# 2_POWER.net
KiCad netlist of a schematic drawn in Altium Designer
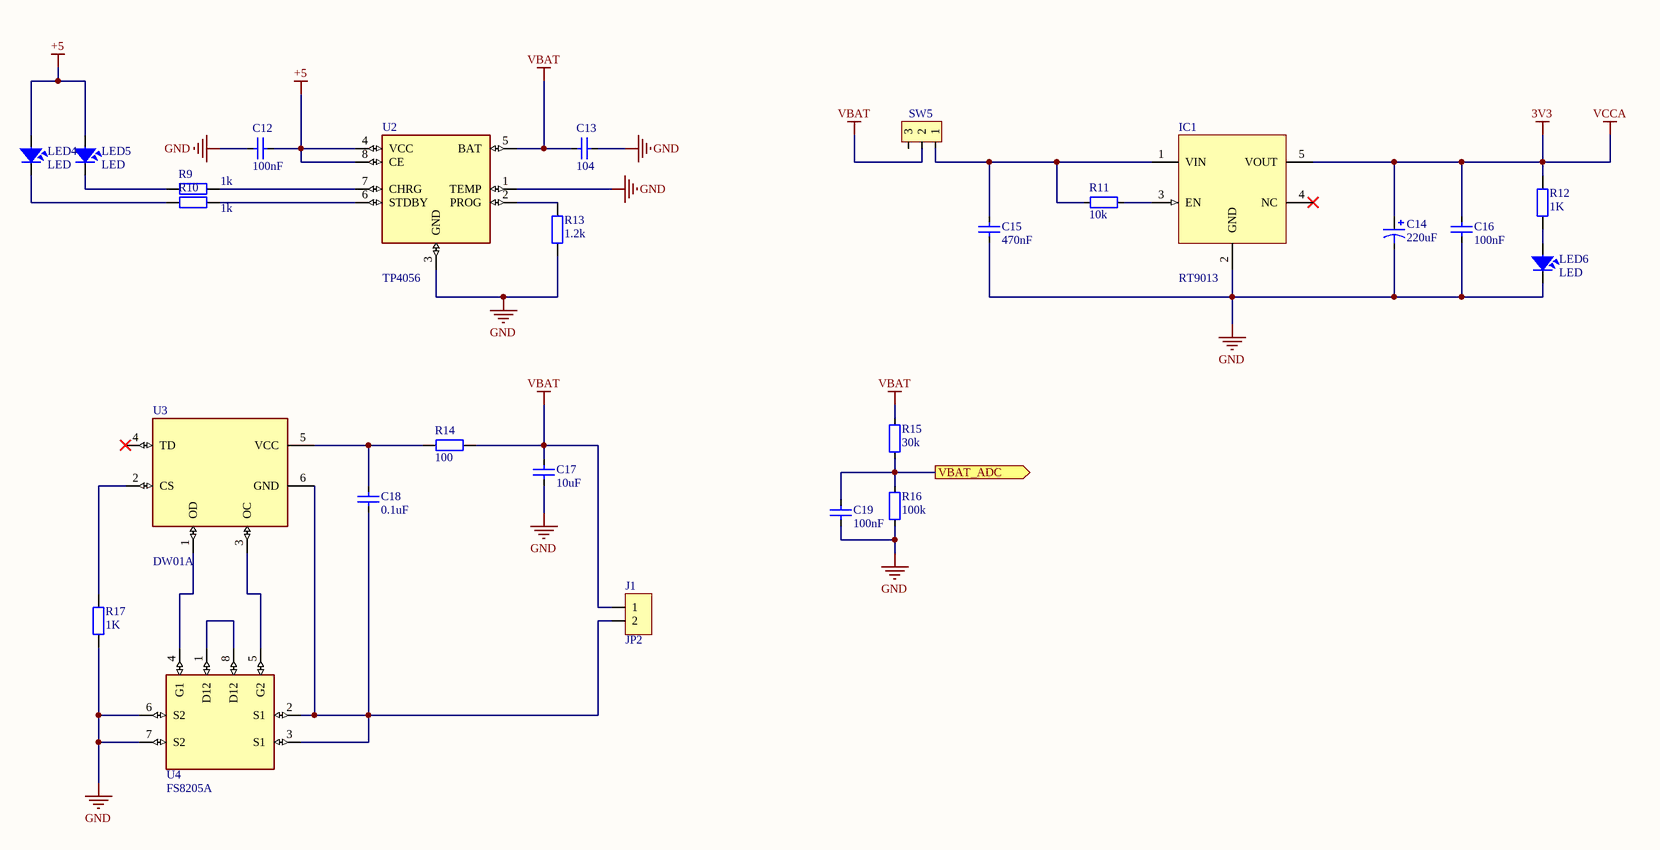
[diagram p0: [2]POWER.SchDoc]

(export (version "E")
  (design (tool "Eeschema 10.0.6"))
  (components
    (comp (ref "C12")
      (value "100nF")
      (footprint "CAP_0805")
      (description "Capacitor")
      (fields (field (name "PUBLISHER") "Altium Limited"))
      (libsource (lib "My Library") (part "CapSMD"))
    )
    (comp (ref "C13")
      (value "104")
      (footprint "CAP_0805")
      (description "Capacitor")
      (fields (field (name "PUBLISHER") "Altium Limited"))
      (libsource (lib "My Library") (part "CapSMD"))
    )
    (comp (ref "C14")
      (value "220uF")
      (footprint "c5mm")
      (description "Polarized Capacitor (Axial)")
      (fields (field (name "PUBLISHER") "Altium Limited"))
      (libsource (lib "My Library") (part "Cap Pol"))
    )
    (comp (ref "C15")
      (value "470nF")
      (footprint "CAP_0805")
      (description "Capacitor")
      (fields (field (name "PUBLISHER") "Altium Limited"))
      (libsource (lib "My Library") (part "CapSMD"))
    )
    (comp (ref "C16")
      (value "100nF")
      (footprint "CAP_0805")
      (description "Capacitor")
      (fields (field (name "PUBLISHER") "Altium Limited"))
      (libsource (lib "My Library") (part "CapSMD"))
    )
    (comp (ref "C17")
      (value "10uF")
      (footprint "CAP_0805")
      (description "Capacitor")
      (fields (field (name "PUBLISHER") "Altium Limited"))
      (libsource (lib "My Library") (part "CapSMD"))
    )
    (comp (ref "C18")
      (value "0.1uF")
      (footprint "CAP_0805")
      (description "Capacitor")
      (fields (field (name "PUBLISHER") "Altium Limited"))
      (libsource (lib "My Library") (part "CapSMD"))
    )
    (comp (ref "C19")
      (value "100nF")
      (footprint "CAP_0805")
      (description "Capacitor")
      (fields (field (name "PUBLISHER") "Altium Limited"))
      (libsource (lib "My Library") (part "CapSMD"))
    )
    (comp (ref "IC1")
      (value "RT9013")
      (footprint "SOT23-5")
      (description "RT9013-33GB IC REG LINEAR 3.3V 500mA SOT23-5")
      (libsource (lib "My Library") (part "RT9013"))
    )
    (comp (ref "J1")
      (value "JP2")
      (footprint "JP2-D1T")
      (description "WR-PHD 2.54 mm Angled Socket Header")
      (fields
        (field (name "MANUFACTURER") "Würth Elektronik eiSos GmbH")
        (field (name "PARTNO") "613002143121")
        (field (name "CREATED BY") "Karrer Zheng")
      )
      (libsource (lib "My Library") (part "JP2"))
    )
    (comp (ref "LED4")
      (value "LED")
      (footprint "LED-0805-Green")
      (description "LED Single colour Green and Red")
      (libsource (lib "My Library") (part "LED"))
    )
    (comp (ref "LED5")
      (value "LED")
      (footprint "LED-0805-Red")
      (description "LED Single colour Green and Red")
      (libsource (lib "My Library") (part "LED"))
    )
    (comp (ref "LED6")
      (value "LED")
      (footprint "LED-0805-Blue")
      (description "LED Single colour Green and Red")
      (libsource (lib "My Library") (part "LED"))
    )
    (comp (ref "R9")
      (value "1k")
      (footprint "RES_SMD_0805")
      (description "Resistor SMD")
      (fields
        (field (name "MANUFACTURER") "Generic Components")
        (field (name "PUBLISHER") "Altium Hobart Technology Centre")
      )
      (libsource (lib "") (part "Resistor - SMD_1"))
    )
    (comp (ref "R10")
      (value "1k")
      (footprint "RES_SMD_0805")
      (description "Resistor SMD")
      (fields
        (field (name "MANUFACTURER") "Generic Components")
        (field (name "PUBLISHER") "Altium Hobart Technology Centre")
      )
      (libsource (lib "") (part "Resistor - SMD_1"))
    )
    (comp (ref "R11")
      (value "10k")
      (footprint "RES_SMD_0805")
      (description "Resistor")
      (fields
        (field (name "MANUFACTURER") "Generic Components")
        (field (name "PUBLISHER") "Altium Hobart Technology Centre")
      )
      (libsource (lib "My Library") (part "Resistor - SMD"))
    )
    (comp (ref "R12")
      (value "1K")
      (footprint "RES-SMD-0805")
      (description "Resistor SMD")
      (fields
        (field (name "MANUFACTURER") "Generic Components")
        (field (name "PUBLISHER") "Altium Hobart Technology Centre")
      )
      (libsource (lib "") (part "Resistor - SMD_1"))
    )
    (comp (ref "R13")
      (value "1.2k")
      (footprint "RES_SMD_0805")
      (description "Resistor SMD")
      (fields
        (field (name "MANUFACTURER") "Generic Components")
        (field (name "PUBLISHER") "Altium Hobart Technology Centre")
      )
      (libsource (lib "") (part "Resistor - SMD_1"))
    )
    (comp (ref "R14")
      (value "100")
      (footprint "RES_SMD_0805")
      (description "Resistor SMD")
      (fields
        (field (name "MANUFACTURER") "Generic Components")
        (field (name "PUBLISHER") "Altium Hobart Technology Centre")
      )
      (libsource (lib "") (part "Resistor - SMD_1"))
    )
    (comp (ref "R15")
      (value "30k")
      (footprint "RES_SMD_0805")
      (description "Resistor")
      (fields
        (field (name "MANUFACTURER") "Generic Components")
        (field (name "PUBLISHER") "Altium Hobart Technology Centre")
      )
      (libsource (lib "My Library") (part "Resistor - SMD"))
    )
    (comp (ref "R16")
      (value "100k")
      (footprint "RES_SMD_0805")
      (description "Resistor")
      (fields
        (field (name "MANUFACTURER") "Generic Components")
        (field (name "PUBLISHER") "Altium Hobart Technology Centre")
      )
      (libsource (lib "My Library") (part "Resistor - SMD"))
    )
    (comp (ref "R17")
      (value "1K")
      (footprint "RES_SMD_0805")
      (description "Resistor SMD")
      (fields
        (field (name "MANUFACTURER") "Generic Components")
        (field (name "PUBLISHER") "Altium Hobart Technology Centre")
      )
      (libsource (lib "") (part "Resistor - SMD_1"))
    )
    (comp (ref "SW5") (value "SW3") (footprint "JP3") (libsource (lib "My Library") (part "SW3")))
    (comp (ref "U2")
      (value "TP4056")
      (footprint "TP4056")
      (description "Complete single cell Li-Ion battery with a constant current / constant voltage linear charger")
      (libsource (lib "My Library") (part "TP4056"))
    )
    (comp (ref "U3")
      (value "DW01A")
      (footprint "SOT23-6")
      (description "One Cell Lithium-ion/Polymer Battery Protection IC")
      (libsource (lib "My Library") (part "DW01A"))
    )
    (comp (ref "U4") (value "FS8205A") (footprint "FS8205A") (libsource (lib "My Library") (part "FS8205A")))
  )
  (nets
    (net (code "1") (name "+5") (class "Default")
      (node (ref "C12") (pin "2") (pinfunction "2_2") (pintype "passive"))
      (node (ref "LED4") (pin "1") (pinfunction "1_1") (pintype "passive"))
      (node (ref "LED5") (pin "1") (pinfunction "1_1") (pintype "passive"))
      (node (ref "U2") (pin "4") (pinfunction "VCC_4") (pintype "bidirectional"))
      (node (ref "U2") (pin "8") (pinfunction "CE_8") (pintype "bidirectional"))
    )
    (net (code "2") (name "/VBAT_ADC") (class "Default")
      (node (ref "C19") (pin "2") (pinfunction "2_2") (pintype "passive"))
      (node (ref "R15") (pin "2") (pinfunction "2_2") (pintype "passive"))
      (node (ref "R16") (pin "1") (pinfunction "1_1") (pintype "passive"))
    )
    (net (code "3") (name "3V3") (class "Default")
      (node (ref "C14") (pin "1") (pinfunction "1_1") (pintype "passive"))
      (node (ref "C16") (pin "1") (pinfunction "1_1") (pintype "passive"))
      (node (ref "IC1") (pin "5") (pinfunction "VOUT_5") (pintype "power_in"))
      (node (ref "R12") (pin "1") (pinfunction "1_1") (pintype "passive"))
    )
    (net (code "4") (name "GND") (class "Default")
      (node (ref "C12") (pin "1") (pinfunction "1_1") (pintype "passive"))
      (node (ref "C13") (pin "2") (pinfunction "2_2") (pintype "passive"))
      (node (ref "C14") (pin "2") (pinfunction "2_2") (pintype "passive"))
      (node (ref "C15") (pin "2") (pinfunction "2_2") (pintype "passive"))
      (node (ref "C16") (pin "2") (pinfunction "2_2") (pintype "passive"))
      (node (ref "C17") (pin "1") (pinfunction "1_1") (pintype "passive"))
      (node (ref "C19") (pin "1") (pinfunction "1_1") (pintype "passive"))
      (node (ref "IC1") (pin "2") (pinfunction "GND_2") (pintype "power_in"))
      (node (ref "LED6") (pin "2") (pinfunction "2_2") (pintype "passive"))
      (node (ref "R13") (pin "2") (pinfunction "2_2") (pintype "passive"))
      (node (ref "R16") (pin "2") (pinfunction "2_2") (pintype "passive"))
      (node (ref "R17") (pin "2") (pinfunction "2_2") (pintype "passive"))
      (node (ref "U2") (pin "1") (pinfunction "TEMP_1") (pintype "bidirectional"))
      (node (ref "U2") (pin "3") (pinfunction "GND_3") (pintype "bidirectional"))
      (node (ref "U4") (pin "6") (pinfunction "S2_6") (pintype "bidirectional"))
      (node (ref "U4") (pin "7") (pinfunction "S2_7") (pintype "bidirectional"))
    )
    (net (code "5") (name "Net-(IC1-EN)") (class "Default")
      (node (ref "IC1") (pin "3") (pinfunction "EN_3") (pintype "input"))
      (node (ref "R11") (pin "1") (pinfunction "1_1") (pintype "passive"))
    )
    (net (code "6") (name "Net-(IC1-VIN)") (class "Default")
      (node (ref "C15") (pin "1") (pinfunction "1_1") (pintype "passive"))
      (node (ref "IC1") (pin "1") (pinfunction "VIN_1") (pintype "power_in"))
      (node (ref "R11") (pin "2") (pinfunction "2_2") (pintype "passive"))
      (node (ref "SW5") (pin "1") (pinfunction "1_1") (pintype "passive"))
    )
    (net (code "7") (name "Net-(LED4-Pad2)") (class "Default")
      (node (ref "LED4") (pin "2") (pinfunction "2_2") (pintype "passive"))
      (node (ref "R10") (pin "2") (pinfunction "2_2") (pintype "passive"))
    )
    (net (code "8") (name "Net-(LED5-Pad2)") (class "Default")
      (node (ref "LED5") (pin "2") (pinfunction "2_2") (pintype "passive"))
      (node (ref "R9") (pin "2") (pinfunction "2_2") (pintype "passive"))
    )
    (net (code "9") (name "Net-(LED6-Pad1)") (class "Default")
      (node (ref "LED6") (pin "1") (pinfunction "1_1") (pintype "passive"))
      (node (ref "R12") (pin "2") (pinfunction "2_2") (pintype "passive"))
    )
    (net (code "10") (name "Net-(U2-CHRG)") (class "Default")
      (node (ref "R9") (pin "1") (pinfunction "1_1") (pintype "passive"))
      (node (ref "U2") (pin "7") (pinfunction "CHRG_7") (pintype "bidirectional"))
    )
    (net (code "11") (name "Net-(U2-PROG)") (class "Default")
      (node (ref "R13") (pin "1") (pinfunction "1_1") (pintype "passive"))
      (node (ref "U2") (pin "2") (pinfunction "PROG_2") (pintype "bidirectional"))
    )
    (net (code "12") (name "Net-(U2-STDBY)") (class "Default")
      (node (ref "R10") (pin "1") (pinfunction "1_1") (pintype "passive"))
      (node (ref "U2") (pin "6") (pinfunction "STDBY_6") (pintype "bidirectional"))
    )
    (net (code "13") (name "Net-(U3-CS)") (class "Default")
      (node (ref "R17") (pin "1") (pinfunction "1_1") (pintype "passive"))
      (node (ref "U3") (pin "2") (pinfunction "CS_2") (pintype "bidirectional"))
    )
    (net (code "14") (name "Net-(U3-GND)") (class "Default")
      (node (ref "C18") (pin "1") (pinfunction "1_1") (pintype "passive"))
      (node (ref "J1") (pin "2") (pinfunction "2_2") (pintype "passive"))
      (node (ref "U3") (pin "6") (pinfunction "GND_6") (pintype "power_in"))
      (node (ref "U4") (pin "2") (pinfunction "S1_2") (pintype "bidirectional"))
      (node (ref "U4") (pin "3") (pinfunction "S1_3") (pintype "bidirectional"))
    )
    (net (code "15") (name "Net-(U3-OC)") (class "Default")
      (node (ref "U3") (pin "3") (pinfunction "OC_3") (pintype "bidirectional"))
      (node (ref "U4") (pin "5") (pinfunction "G2_5") (pintype "bidirectional"))
    )
    (net (code "16") (name "Net-(U3-OD)") (class "Default")
      (node (ref "U3") (pin "1") (pinfunction "OD_1") (pintype "bidirectional"))
      (node (ref "U4") (pin "4") (pinfunction "G1_4") (pintype "bidirectional"))
    )
    (net (code "17") (name "Net-(U3-VCC)") (class "Default")
      (node (ref "C18") (pin "2") (pinfunction "2_2") (pintype "passive"))
      (node (ref "R14") (pin "2") (pinfunction "2_2") (pintype "passive"))
      (node (ref "U3") (pin "5") (pinfunction "VCC_5") (pintype "power_in"))
    )
    (net (code "18") (name "Net-(U4-D12-Pad1)") (class "Default")
      (node (ref "U4") (pin "1") (pinfunction "D12_1") (pintype "bidirectional"))
      (node (ref "U4") (pin "8") (pinfunction "D12_8") (pintype "bidirectional"))
    )
    (net (code "19") (name "VBAT") (class "Default")
      (node (ref "C13") (pin "1") (pinfunction "1_1") (pintype "passive"))
      (node (ref "C17") (pin "2") (pinfunction "2_2") (pintype "passive"))
      (node (ref "J1") (pin "1") (pinfunction "1_1") (pintype "passive"))
      (node (ref "R14") (pin "1") (pinfunction "1_1") (pintype "passive"))
      (node (ref "R15") (pin "1") (pinfunction "1_1") (pintype "passive"))
      (node (ref "SW5") (pin "2") (pinfunction "2_2") (pintype "passive"))
      (node (ref "U2") (pin "5") (pinfunction "BAT_5") (pintype "bidirectional"))
    )
    (net (code "20") (name "unconnected-(IC1-NC-Pad4)") (class "Default")
      (node (ref "IC1") (pin "4") (pinfunction "NC_4") (pintype "passive+no_connect"))
    )
    (net (code "21") (name "unconnected-(SW5-Pad3)") (class "Default")
      (node (ref "SW5") (pin "3") (pinfunction "3_3") (pintype "passive"))
    )
    (net (code "22") (name "unconnected-(U3-TD-Pad4)") (class "Default")
      (node (ref "U3") (pin "4") (pinfunction "TD_4") (pintype "bidirectional+no_connect"))
    )
  )
)
